# 02_Connectors.net
KiCad netlist of a schematic drawn in Altium Designer
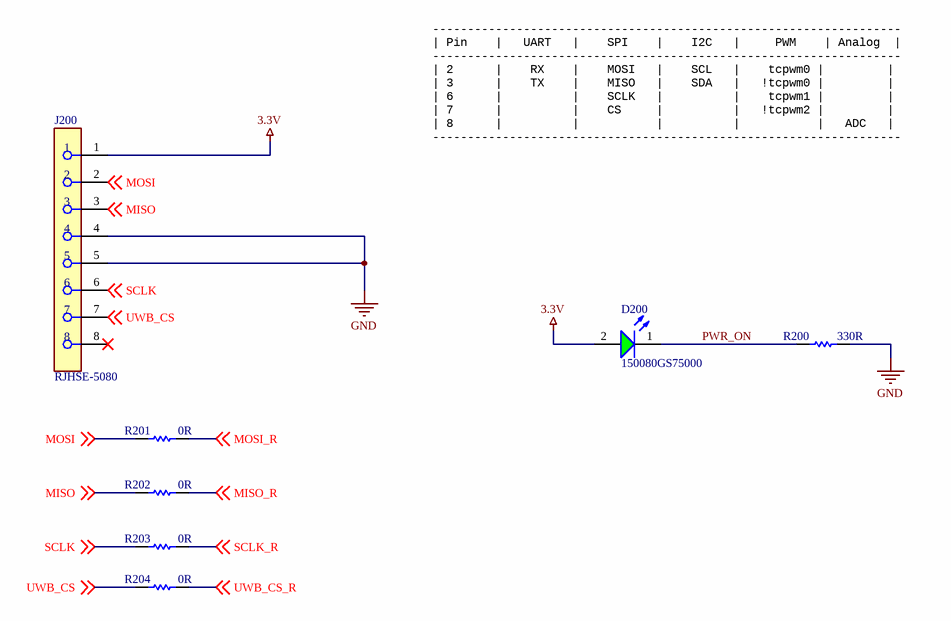
[diagram p0: 02_Connectors.SchDoc]

(export (version "E")
  (design (tool "Eeschema 10.0.6"))
  (components
    (comp (ref "D200")
      (value "150080GS75000")
      (footprint "WL-SMCW_0805_150080xx75000")
      (fields (field (name "MANUFACTURER") "Wurth Electronics"))
      (libsource (lib "Altium Content Vault") (part "LED_Green_2A-1K"))
    )
    (comp (ref "J200")
      (value "RJHSE-5080")
      (footprint "FP-RJHSE-5080-MFG")
      (description "CONN MOD JACK 8P8C R/A UNSHLD")
      (fields
        (field (name "OCTOPART") "https://octopart.com/rjhse-5080-amphenol-45060")
        (field (name "MANUFACTURER") "Amphenol")
      )
      (libsource (lib "Altium Content Vault") (part "b0a0b555dd3abf3683e7c330df25cc4"))
    )
    (comp (ref "R200")
      (value "330R")
      (footprint "RESC2013X60X40LL20T25")
      (fields
        (field (name "MANUFACTURER") "Panasonic")
        (field (name "PART NUMBER") "ERA6AEB331V")
        (field (name "MANUFACTURER PART NUMBER") "ERA-6AEB331V")
      )
      (libsource (lib "Altium Content Vault") (part "RES"))
    )
    (comp (ref "R201")
      (value "0R")
      (footprint "RESC2013X70X40NL20T20")
      (description "Chip Resistor, 0 Ohm, +/- 1%, 0.125 W, -55 to 155 degC, 0805 (2012 Metric), RoHS, Tape and Reel")
      (fields (field (name "PARTNUMBER") "ERJ-6GEY0R00V") (field (name "TOLERANCE") "5%"))
      (libsource (lib "Altium Content Vault") (part "RES-2"))
    )
    (comp (ref "R202")
      (value "0R")
      (footprint "RESC2013X70X40NL20T20")
      (description "Chip Resistor, 0 Ohm, +/- 1%, 0.125 W, -55 to 155 degC, 0805 (2012 Metric), RoHS, Tape and Reel")
      (fields (field (name "PARTNUMBER") "ERJ-6GEY0R00V") (field (name "TOLERANCE") "5%"))
      (libsource (lib "Altium Content Vault") (part "RES-2"))
    )
    (comp (ref "R203")
      (value "0R")
      (footprint "RESC2013X70X40NL20T20")
      (description "Chip Resistor, 0 Ohm, +/- 1%, 0.125 W, -55 to 155 degC, 0805 (2012 Metric), RoHS, Tape and Reel")
      (fields (field (name "PARTNUMBER") "ERJ-6GEY0R00V") (field (name "TOLERANCE") "5%"))
      (libsource (lib "Altium Content Vault") (part "RES-2"))
    )
    (comp (ref "R204")
      (value "0R")
      (footprint "RESC2013X70X40NL20T20")
      (description "Chip Resistor, 0 Ohm, +/- 1%, 0.125 W, -55 to 155 degC, 0805 (2012 Metric), RoHS, Tape and Reel")
      (fields (field (name "PARTNUMBER") "ERJ-6GEY0R00V") (field (name "TOLERANCE") "5%"))
      (libsource (lib "Altium Content Vault") (part "RES-2"))
    )
  )
  (nets
    (net (code "1") (name "/PWR_ON") (class "Default")
      (node (ref "D200") (pin "1") (pinfunction "K_1") (pintype "passive"))
      (node (ref "R200") (pin "1") (pinfunction "1_1") (pintype "passive"))
    )
    (net (code "2") (name "3.3V") (class "Default")
      (node (ref "D200") (pin "2") (pinfunction "A_2") (pintype "passive"))
      (node (ref "J200") (pin "1") (pinfunction "1_1") (pintype "passive"))
    )
    (net (code "3") (name "GND") (class "Default")
      (node (ref "J200") (pin "4") (pinfunction "4_4") (pintype "passive"))
      (node (ref "J200") (pin "5") (pinfunction "5_5") (pintype "passive"))
      (node (ref "R200") (pin "2") (pinfunction "2_2") (pintype "passive"))
    )
    (net (code "4") (name "MISO") (class "Default")
      (node (ref "J200") (pin "3") (pinfunction "3_3") (pintype "passive"))
      (node (ref "R202") (pin "1") (pinfunction "1_1") (pintype "passive"))
    )
    (net (code "5") (name "MISO_R") (class "Default")
      (node (ref "R202") (pin "2") (pinfunction "2_2") (pintype "passive"))
    )
    (net (code "6") (name "MOSI") (class "Default")
      (node (ref "J200") (pin "2") (pinfunction "2_2") (pintype "passive"))
      (node (ref "R201") (pin "1") (pinfunction "1_1") (pintype "passive"))
    )
    (net (code "7") (name "MOSI_R") (class "Default")
      (node (ref "R201") (pin "2") (pinfunction "2_2") (pintype "passive"))
    )
    (net (code "8") (name "SCLK") (class "Default")
      (node (ref "J200") (pin "6") (pinfunction "6_6") (pintype "passive"))
      (node (ref "R203") (pin "1") (pinfunction "1_1") (pintype "passive"))
    )
    (net (code "9") (name "SCLK_R") (class "Default")
      (node (ref "R203") (pin "2") (pinfunction "2_2") (pintype "passive"))
    )
    (net (code "10") (name "UWB_CS") (class "Default")
      (node (ref "J200") (pin "7") (pinfunction "7_7") (pintype "passive"))
      (node (ref "R204") (pin "1") (pinfunction "1_1") (pintype "passive"))
    )
    (net (code "11") (name "UWB_CS_R") (class "Default")
      (node (ref "R204") (pin "2") (pinfunction "2_2") (pintype "passive"))
    )
    (net (code "12") (name "unconnected-(J200-Pad8)") (class "Default")
      (node (ref "J200") (pin "8") (pinfunction "8_8") (pintype "passive+no_connect"))
    )
  )
)
